# M164B.net
KiCad netlist of a schematic drawn in EAGLE
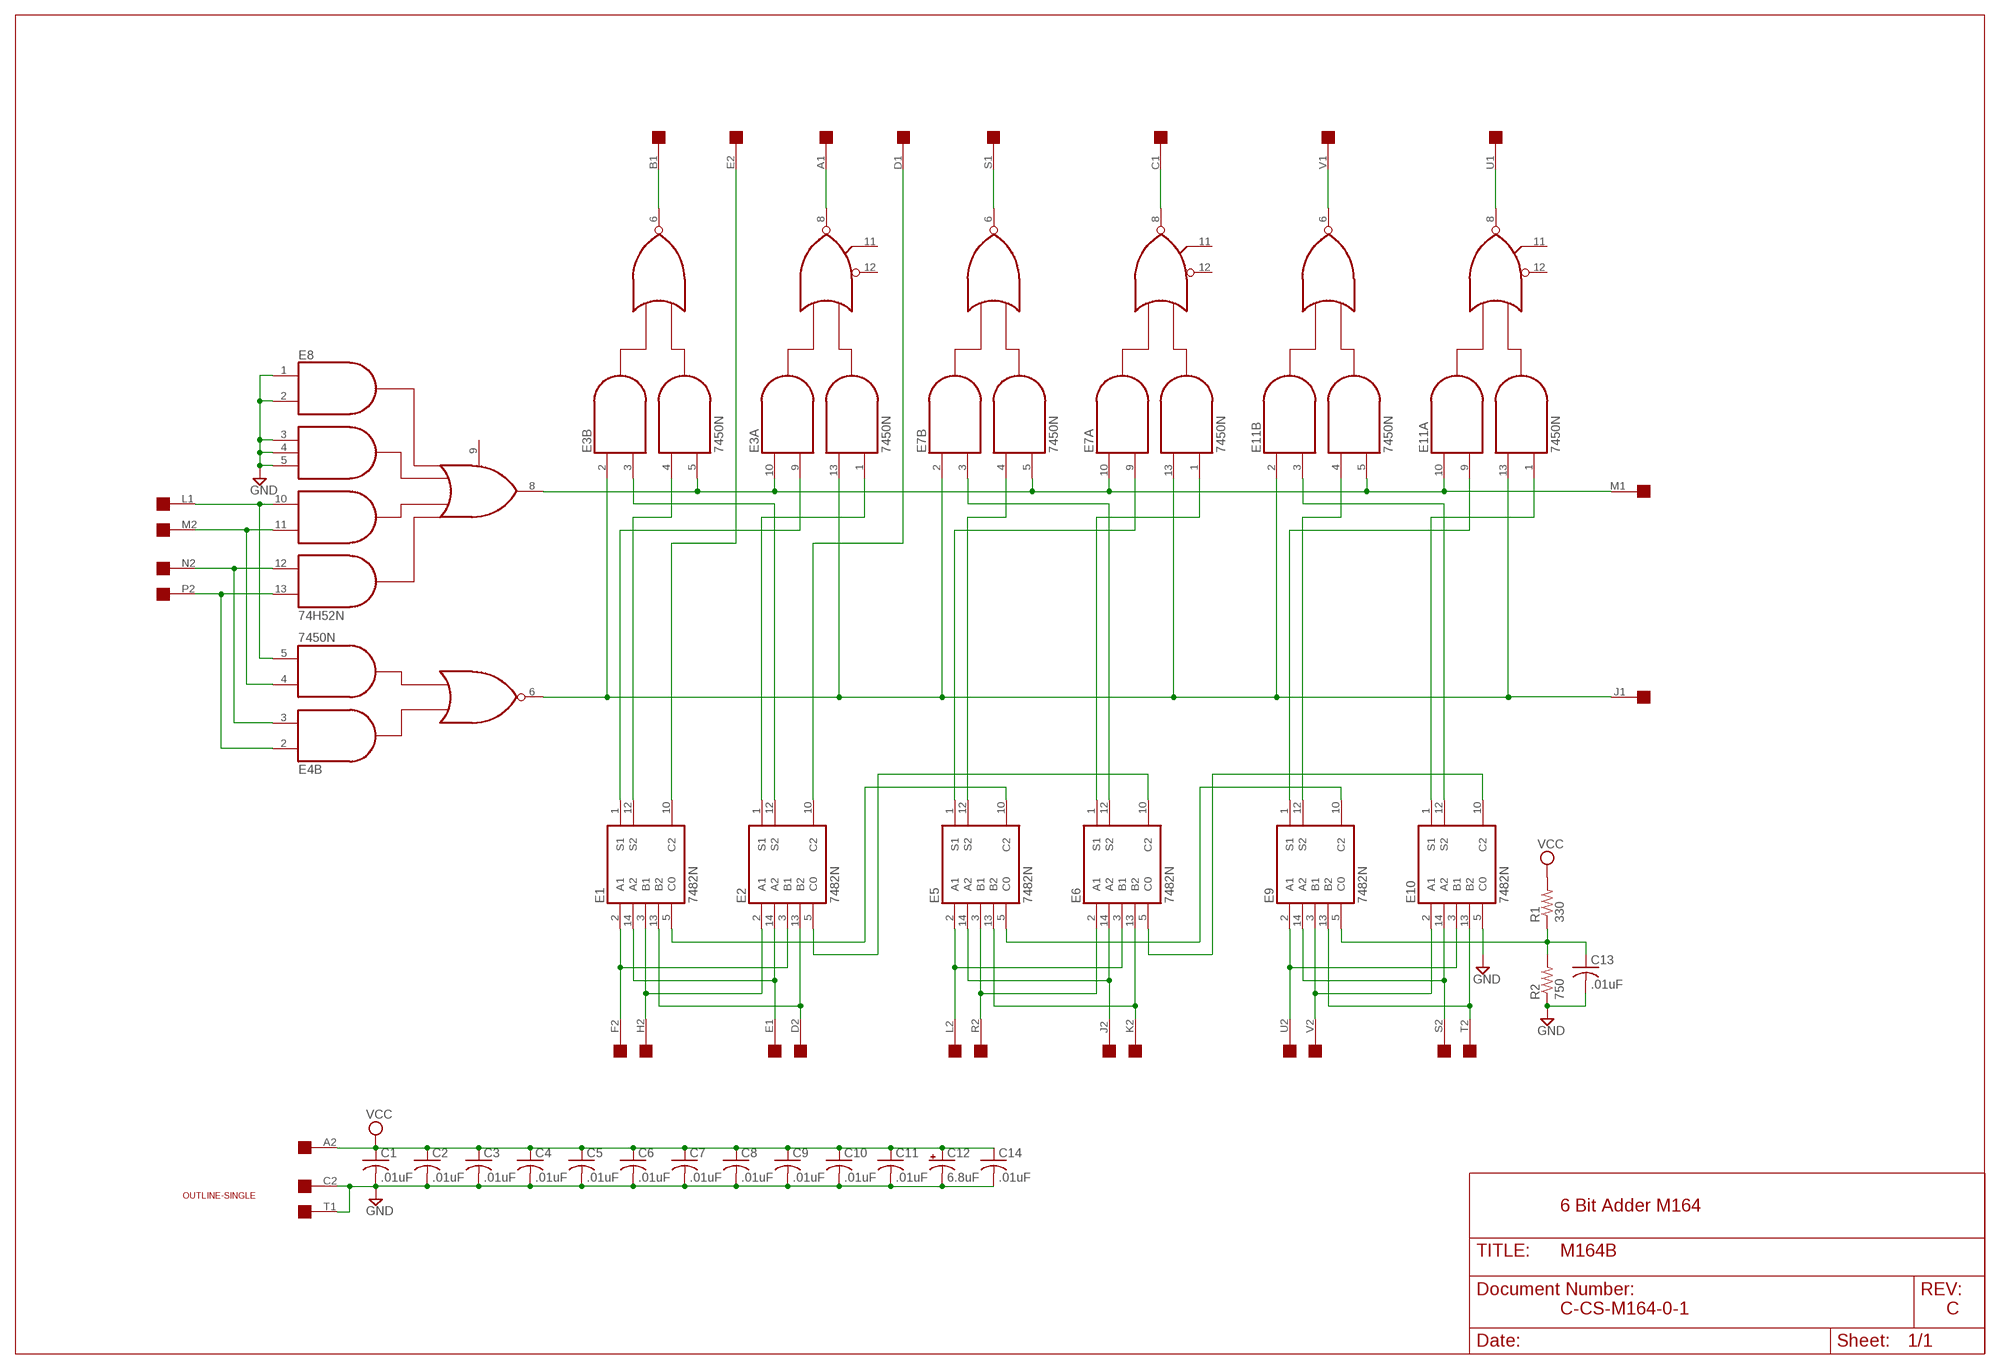
[diagram p0: schematic, sheet 1]

(export (version "E")
  (design (tool "Eeschema 10.0.6"))
  (components
    (comp (ref "C1")
      (value ".01uF")
      (footprint "eagle-import:C050-025X075")
      (libsource (lib "eagle-import") (part "C-US050-025X075"))
    )
    (comp (ref "C2")
      (value ".01uF")
      (footprint "eagle-import:C050-025X075")
      (libsource (lib "eagle-import") (part "C-US050-025X075"))
    )
    (comp (ref "C3")
      (value ".01uF")
      (footprint "eagle-import:C050-025X075")
      (libsource (lib "eagle-import") (part "C-US050-025X075"))
    )
    (comp (ref "C4")
      (value ".01uF")
      (footprint "eagle-import:C050-025X075")
      (libsource (lib "eagle-import") (part "C-US050-025X075"))
    )
    (comp (ref "C5")
      (value ".01uF")
      (footprint "eagle-import:C050-025X075")
      (libsource (lib "eagle-import") (part "C-US050-025X075"))
    )
    (comp (ref "C6")
      (value ".01uF")
      (footprint "eagle-import:C050-025X075")
      (libsource (lib "eagle-import") (part "C-US050-025X075"))
    )
    (comp (ref "C7")
      (value ".01uF")
      (footprint "eagle-import:C050-025X075")
      (libsource (lib "eagle-import") (part "C-US050-025X075"))
    )
    (comp (ref "C8")
      (value ".01uF")
      (footprint "eagle-import:C050-025X075")
      (libsource (lib "eagle-import") (part "C-US050-025X075"))
    )
    (comp (ref "C9")
      (value ".01uF")
      (footprint "eagle-import:C050-025X075")
      (libsource (lib "eagle-import") (part "C-US050-025X075"))
    )
    (comp (ref "C10")
      (value ".01uF")
      (footprint "eagle-import:C050-025X075")
      (libsource (lib "eagle-import") (part "C-US050-025X075"))
    )
    (comp (ref "C11")
      (value ".01uF")
      (footprint "eagle-import:C050-025X075")
      (libsource (lib "eagle-import") (part "C-US050-025X075"))
    )
    (comp (ref "C12")
      (value "6.8uF")
      (footprint "eagle-import:E12-8")
      (libsource (lib "eagle-import") (part "CPOL-USE20-8AXIAL"))
    )
    (comp (ref "C13")
      (value ".01uF")
      (footprint "eagle-import:C050-025X075")
      (libsource (lib "eagle-import") (part "C-US050-025X075"))
    )
    (comp (ref "C14")
      (value ".01uF")
      (footprint "eagle-import:C050-025X075")
      (libsource (lib "eagle-import") (part "C-US050-025X075"))
    )
    (comp (ref "E1")
      (value "7482N")
      (footprint "eagle-import:DIL14")
      (libsource (lib "eagle-import") (part "7482N"))
    )
    (comp (ref "E2")
      (value "7482N")
      (footprint "eagle-import:DIL14")
      (libsource (lib "eagle-import") (part "7482N"))
    )
    (comp (ref "E3")
      (value "7450N")
      (footprint "eagle-import:DIL14")
      (libsource (lib "eagle-import") (part "7450N"))
    )
    (comp (ref "E4")
      (value "7450N")
      (footprint "eagle-import:DIL14")
      (libsource (lib "eagle-import") (part "7450N"))
    )
    (comp (ref "E5")
      (value "7482N")
      (footprint "eagle-import:DIL14")
      (libsource (lib "eagle-import") (part "7482N"))
    )
    (comp (ref "E6")
      (value "7482N")
      (footprint "eagle-import:DIL14")
      (libsource (lib "eagle-import") (part "7482N"))
    )
    (comp (ref "E7")
      (value "7450N")
      (footprint "eagle-import:DIL14")
      (libsource (lib "eagle-import") (part "7450N"))
    )
    (comp (ref "E8")
      (value "74H52N")
      (footprint "eagle-import:DIL14")
      (libsource (lib "eagle-import") (part "7452H"))
    )
    (comp (ref "E9")
      (value "7482N")
      (footprint "eagle-import:DIL14")
      (libsource (lib "eagle-import") (part "7482N"))
    )
    (comp (ref "E10")
      (value "7482N")
      (footprint "eagle-import:DIL14")
      (libsource (lib "eagle-import") (part "7482N"))
    )
    (comp (ref "E11")
      (value "7450N")
      (footprint "eagle-import:DIL14")
      (libsource (lib "eagle-import") (part "7450N"))
    )
    (comp (ref "R1")
      (value "330")
      (footprint "eagle-import:0207_10")
      (libsource (lib "eagle-import") (part "R-US_0207/10"))
    )
    (comp (ref "R2")
      (value "750")
      (footprint "eagle-import:0207_10")
      (libsource (lib "eagle-import") (part "R-US_0207/10"))
    )
    (comp (ref "U$1")
      (value "SINGLE")
      (footprint "eagle-import:EDGE-CON2")
      (libsource (lib "eagle-import") (part "SINGLE"))
    )
    (comp (ref "U$2")
      (value "OUTLINE-SINGLE")
      (footprint "eagle-import:SINGLE")
      (libsource (lib "eagle-import") (part "OUTLINE-SINGLE"))
    )
  )
  (nets
    (net (code "1") (name "GND") (class "Default")
      (node (ref "C1") (pin "2") (pinfunction "2_2") (pintype "passive"))
      (node (ref "C10") (pin "2") (pinfunction "2_2") (pintype "passive"))
      (node (ref "C11") (pin "2") (pinfunction "2_2") (pintype "passive"))
      (node (ref "C12") (pin "-") (pinfunction "-_-") (pintype "passive"))
      (node (ref "C13") (pin "2") (pinfunction "2_2") (pintype "passive"))
      (node (ref "C14") (pin "2") (pinfunction "2_2") (pintype "passive"))
      (node (ref "C2") (pin "2") (pinfunction "2_2") (pintype "passive"))
      (node (ref "C3") (pin "2") (pinfunction "2_2") (pintype "passive"))
      (node (ref "C4") (pin "2") (pinfunction "2_2") (pintype "passive"))
      (node (ref "C5") (pin "2") (pinfunction "2_2") (pintype "passive"))
      (node (ref "C6") (pin "2") (pinfunction "2_2") (pintype "passive"))
      (node (ref "C7") (pin "2") (pinfunction "2_2") (pintype "passive"))
      (node (ref "C8") (pin "2") (pinfunction "2_2") (pintype "passive"))
      (node (ref "C9") (pin "2") (pinfunction "2_2") (pintype "passive"))
      (node (ref "E10") (pin "5") (pinfunction "C0_5") (pintype "input"))
      (node (ref "E8") (pin "1") (pinfunction "I1_1") (pintype "input"))
      (node (ref "E8") (pin "2") (pinfunction "I2_2") (pintype "input"))
      (node (ref "E8") (pin "3") (pinfunction "I3_3") (pintype "input"))
      (node (ref "E8") (pin "4") (pinfunction "I4_4") (pintype "input"))
      (node (ref "E8") (pin "5") (pinfunction "I5_5") (pintype "input"))
      (node (ref "R2") (pin "1") (pinfunction "1_1") (pintype "passive"))
      (node (ref "U$1") (pin "C2") (pinfunction "1_C2") (pintype "bidirectional"))
      (node (ref "U$1") (pin "T1") (pinfunction "1_T1") (pintype "bidirectional"))
    )
    (net (code "2") (name "Net-(E1E-A1)") (class "Default")
      (node (ref "E1") (pin "2") (pinfunction "A1_2") (pintype "input"))
      (node (ref "E2") (pin "3") (pinfunction "B1_3") (pintype "input"))
      (node (ref "U$1") (pin "F2") (pinfunction "1_F2") (pintype "bidirectional"))
    )
    (net (code "3") (name "Net-(E1E-A2)") (class "Default")
      (node (ref "E1") (pin "14") (pinfunction "A2_14") (pintype "input"))
      (node (ref "E2") (pin "14") (pinfunction "A2_14") (pintype "input"))
      (node (ref "U$1") (pin "E1") (pinfunction "1_E1") (pintype "bidirectional"))
    )
    (net (code "4") (name "Net-(E1E-B1)") (class "Default")
      (node (ref "E1") (pin "3") (pinfunction "B1_3") (pintype "input"))
      (node (ref "E2") (pin "2") (pinfunction "A1_2") (pintype "input"))
      (node (ref "U$1") (pin "H2") (pinfunction "1_H2") (pintype "bidirectional"))
    )
    (net (code "5") (name "Net-(E1E-B2)") (class "Default")
      (node (ref "E1") (pin "13") (pinfunction "B2_13") (pintype "input"))
      (node (ref "E2") (pin "13") (pinfunction "B2_13") (pintype "input"))
      (node (ref "U$1") (pin "D2") (pinfunction "1_D2") (pintype "bidirectional"))
    )
    (net (code "6") (name "Net-(E1E-C0)") (class "Default")
      (node (ref "E1") (pin "5") (pinfunction "C0_5") (pintype "input"))
      (node (ref "E5") (pin "10") (pinfunction "C2_10") (pintype "output"))
    )
    (net (code "7") (name "Net-(E1E-C2)") (class "Default")
      (node (ref "E1") (pin "10") (pinfunction "C2_10") (pintype "output"))
      (node (ref "U$1") (pin "E2") (pinfunction "1_E2") (pintype "bidirectional"))
    )
    (net (code "8") (name "Net-(E1E-S1)") (class "Default")
      (node (ref "E1") (pin "1") (pinfunction "S1_1") (pintype "output"))
      (node (ref "E3") (pin "9") (pinfunction "I2_9") (pintype "input"))
    )
    (net (code "9") (name "Net-(E1E-S2)") (class "Default")
      (node (ref "E1") (pin "12") (pinfunction "S2_12") (pintype "output"))
      (node (ref "E3") (pin "4") (pinfunction "I3_4") (pintype "input"))
    )
    (net (code "10") (name "Net-(E2E-C0)") (class "Default")
      (node (ref "E2") (pin "5") (pinfunction "C0_5") (pintype "input"))
      (node (ref "E6") (pin "10") (pinfunction "C2_10") (pintype "output"))
    )
    (net (code "11") (name "Net-(E2E-C2)") (class "Default")
      (node (ref "E2") (pin "10") (pinfunction "C2_10") (pintype "output"))
      (node (ref "U$1") (pin "D1") (pinfunction "1_D1") (pintype "bidirectional"))
    )
    (net (code "12") (name "Net-(E2E-S1)") (class "Default")
      (node (ref "E2") (pin "1") (pinfunction "S1_1") (pintype "output"))
      (node (ref "E3") (pin "1") (pinfunction "I4_1") (pintype "input"))
    )
    (net (code "13") (name "Net-(E2E-S2)") (class "Default")
      (node (ref "E2") (pin "12") (pinfunction "S2_12") (pintype "output"))
      (node (ref "E3") (pin "3") (pinfunction "I2_3") (pintype "input"))
    )
    (net (code "14") (name "Net-(E3A-O)") (class "Default")
      (node (ref "E3") (pin "8") (pinfunction "O_8") (pintype "output"))
      (node (ref "U$1") (pin "A1") (pinfunction "1_A1") (pintype "bidirectional"))
    )
    (net (code "15") (name "Net-(E3B-O)") (class "Default")
      (node (ref "E3") (pin "6") (pinfunction "O_6") (pintype "output"))
      (node (ref "U$1") (pin "B1") (pinfunction "1_B1") (pintype "bidirectional"))
    )
    (net (code "16") (name "Net-(E4B-I1)") (class "Default")
      (node (ref "E4") (pin "2") (pinfunction "I1_2") (pintype "input"))
      (node (ref "E8") (pin "13") (pinfunction "I13_13") (pintype "passive"))
      (node (ref "U$1") (pin "P2") (pinfunction "1_P2") (pintype "bidirectional"))
    )
    (net (code "17") (name "Net-(E4B-I2)") (class "Default")
      (node (ref "E4") (pin "3") (pinfunction "I2_3") (pintype "input"))
      (node (ref "E8") (pin "12") (pinfunction "I12_12") (pintype "input"))
      (node (ref "U$1") (pin "N2") (pinfunction "1_N2") (pintype "bidirectional"))
    )
    (net (code "18") (name "Net-(E4B-I3)") (class "Default")
      (node (ref "E4") (pin "4") (pinfunction "I3_4") (pintype "input"))
      (node (ref "E8") (pin "11") (pinfunction "I11_11") (pintype "input"))
      (node (ref "U$1") (pin "M2") (pinfunction "1_M2") (pintype "bidirectional"))
    )
    (net (code "19") (name "Net-(E4B-I4)") (class "Default")
      (node (ref "E4") (pin "5") (pinfunction "I4_5") (pintype "input"))
      (node (ref "E8") (pin "10") (pinfunction "I10_10") (pintype "input"))
      (node (ref "U$1") (pin "L1") (pinfunction "1_L1") (pintype "bidirectional"))
    )
    (net (code "20") (name "Net-(E5E-A1)") (class "Default")
      (node (ref "E5") (pin "2") (pinfunction "A1_2") (pintype "input"))
      (node (ref "E6") (pin "3") (pinfunction "B1_3") (pintype "input"))
      (node (ref "U$1") (pin "L2") (pinfunction "1_L2") (pintype "bidirectional"))
    )
    (net (code "21") (name "Net-(E5E-A2)") (class "Default")
      (node (ref "E5") (pin "14") (pinfunction "A2_14") (pintype "input"))
      (node (ref "E6") (pin "14") (pinfunction "A2_14") (pintype "input"))
      (node (ref "U$1") (pin "J2") (pinfunction "1_J2") (pintype "bidirectional"))
    )
    (net (code "22") (name "Net-(E5E-B1)") (class "Default")
      (node (ref "E5") (pin "3") (pinfunction "B1_3") (pintype "input"))
      (node (ref "E6") (pin "2") (pinfunction "A1_2") (pintype "input"))
      (node (ref "U$1") (pin "R2") (pinfunction "1_R2") (pintype "bidirectional"))
    )
    (net (code "23") (name "Net-(E5E-B2)") (class "Default")
      (node (ref "E5") (pin "13") (pinfunction "B2_13") (pintype "input"))
      (node (ref "E6") (pin "13") (pinfunction "B2_13") (pintype "input"))
      (node (ref "U$1") (pin "K2") (pinfunction "1_K2") (pintype "bidirectional"))
    )
    (net (code "24") (name "Net-(E5E-C0)") (class "Default")
      (node (ref "E5") (pin "5") (pinfunction "C0_5") (pintype "input"))
      (node (ref "E9") (pin "10") (pinfunction "C2_10") (pintype "output"))
    )
    (net (code "25") (name "Net-(E5E-S1)") (class "Default")
      (node (ref "E5") (pin "1") (pinfunction "S1_1") (pintype "output"))
      (node (ref "E7") (pin "9") (pinfunction "I2_9") (pintype "input"))
    )
    (net (code "26") (name "Net-(E5E-S2)") (class "Default")
      (node (ref "E5") (pin "12") (pinfunction "S2_12") (pintype "output"))
      (node (ref "E7") (pin "4") (pinfunction "I3_4") (pintype "input"))
    )
    (net (code "27") (name "Net-(E6E-S1)") (class "Default")
      (node (ref "E6") (pin "1") (pinfunction "S1_1") (pintype "output"))
      (node (ref "E7") (pin "1") (pinfunction "I4_1") (pintype "input"))
    )
    (net (code "28") (name "Net-(E6E-S2)") (class "Default")
      (node (ref "E6") (pin "12") (pinfunction "S2_12") (pintype "output"))
      (node (ref "E7") (pin "3") (pinfunction "I2_3") (pintype "input"))
    )
    (net (code "29") (name "Net-(E7A-O)") (class "Default")
      (node (ref "E7") (pin "8") (pinfunction "O_8") (pintype "output"))
      (node (ref "U$1") (pin "C1") (pinfunction "1_C1") (pintype "bidirectional"))
    )
    (net (code "30") (name "Net-(E7B-O)") (class "Default")
      (node (ref "E7") (pin "6") (pinfunction "O_6") (pintype "output"))
      (node (ref "U$1") (pin "S1") (pinfunction "1_S1") (pintype "bidirectional"))
    )
    (net (code "31") (name "Net-(E9E-C0)") (class "Default")
      (node (ref "C13") (pin "1") (pinfunction "1_1") (pintype "passive"))
      (node (ref "E9") (pin "5") (pinfunction "C0_5") (pintype "input"))
      (node (ref "R1") (pin "1") (pinfunction "1_1") (pintype "passive"))
      (node (ref "R2") (pin "2") (pinfunction "2_2") (pintype "passive"))
    )
    (net (code "32") (name "Net-(E10E-A1)") (class "Default")
      (node (ref "E10") (pin "2") (pinfunction "A1_2") (pintype "input"))
      (node (ref "E9") (pin "3") (pinfunction "B1_3") (pintype "input"))
      (node (ref "U$1") (pin "V2") (pinfunction "1_V2") (pintype "bidirectional"))
    )
    (net (code "33") (name "Net-(E10E-A2)") (class "Default")
      (node (ref "E10") (pin "14") (pinfunction "A2_14") (pintype "input"))
      (node (ref "E9") (pin "14") (pinfunction "A2_14") (pintype "input"))
      (node (ref "U$1") (pin "S2") (pinfunction "1_S2") (pintype "bidirectional"))
    )
    (net (code "34") (name "Net-(E10E-B1)") (class "Default")
      (node (ref "E10") (pin "3") (pinfunction "B1_3") (pintype "input"))
      (node (ref "E9") (pin "2") (pinfunction "A1_2") (pintype "input"))
      (node (ref "U$1") (pin "U2") (pinfunction "1_U2") (pintype "bidirectional"))
    )
    (net (code "35") (name "Net-(E10E-B2)") (class "Default")
      (node (ref "E10") (pin "13") (pinfunction "B2_13") (pintype "input"))
      (node (ref "E9") (pin "13") (pinfunction "B2_13") (pintype "input"))
      (node (ref "U$1") (pin "T2") (pinfunction "1_T2") (pintype "bidirectional"))
    )
    (net (code "36") (name "Net-(E10E-C2)") (class "Default")
      (node (ref "E10") (pin "10") (pinfunction "C2_10") (pintype "output"))
      (node (ref "E6") (pin "5") (pinfunction "C0_5") (pintype "input"))
    )
    (net (code "37") (name "Net-(E10E-S1)") (class "Default")
      (node (ref "E10") (pin "1") (pinfunction "S1_1") (pintype "output"))
      (node (ref "E11") (pin "1") (pinfunction "I4_1") (pintype "input"))
    )
    (net (code "38") (name "Net-(E10E-S2)") (class "Default")
      (node (ref "E10") (pin "12") (pinfunction "S2_12") (pintype "output"))
      (node (ref "E11") (pin "3") (pinfunction "I2_3") (pintype "input"))
    )
    (net (code "39") (name "Net-(E11A-I1)") (class "Default")
      (node (ref "E11") (pin "10") (pinfunction "I1_10") (pintype "input"))
      (node (ref "E11") (pin "5") (pinfunction "I4_5") (pintype "input"))
      (node (ref "E3") (pin "10") (pinfunction "I1_10") (pintype "input"))
      (node (ref "E3") (pin "5") (pinfunction "I4_5") (pintype "input"))
      (node (ref "E7") (pin "10") (pinfunction "I1_10") (pintype "input"))
      (node (ref "E7") (pin "5") (pinfunction "I4_5") (pintype "input"))
      (node (ref "E8") (pin "8") (pinfunction "O8_8") (pintype "output"))
      (node (ref "U$1") (pin "M1") (pinfunction "1_M1") (pintype "bidirectional"))
    )
    (net (code "40") (name "Net-(E11A-I2)") (class "Default")
      (node (ref "E11") (pin "9") (pinfunction "I2_9") (pintype "input"))
      (node (ref "E9") (pin "1") (pinfunction "S1_1") (pintype "output"))
    )
    (net (code "41") (name "Net-(E11A-I3)") (class "Default")
      (node (ref "E11") (pin "13") (pinfunction "I3_13") (pintype "input"))
      (node (ref "E11") (pin "2") (pinfunction "I1_2") (pintype "input"))
      (node (ref "E3") (pin "13") (pinfunction "I3_13") (pintype "input"))
      (node (ref "E3") (pin "2") (pinfunction "I1_2") (pintype "input"))
      (node (ref "E4") (pin "6") (pinfunction "O_6") (pintype "output"))
      (node (ref "E7") (pin "13") (pinfunction "I3_13") (pintype "input"))
      (node (ref "E7") (pin "2") (pinfunction "I1_2") (pintype "input"))
      (node (ref "U$1") (pin "J1") (pinfunction "1_J1") (pintype "bidirectional"))
    )
    (net (code "42") (name "Net-(E11A-O)") (class "Default")
      (node (ref "E11") (pin "8") (pinfunction "O_8") (pintype "output"))
      (node (ref "U$1") (pin "U1") (pinfunction "1_U1") (pintype "bidirectional"))
    )
    (net (code "43") (name "Net-(E11B-I3)") (class "Default")
      (node (ref "E11") (pin "4") (pinfunction "I3_4") (pintype "input"))
      (node (ref "E9") (pin "12") (pinfunction "S2_12") (pintype "output"))
    )
    (net (code "44") (name "Net-(E11B-O)") (class "Default")
      (node (ref "E11") (pin "6") (pinfunction "O_6") (pintype "output"))
      (node (ref "U$1") (pin "V1") (pinfunction "1_V1") (pintype "bidirectional"))
    )
    (net (code "45") (name "VCC") (class "Default")
      (node (ref "C1") (pin "1") (pinfunction "1_1") (pintype "passive"))
      (node (ref "C10") (pin "1") (pinfunction "1_1") (pintype "passive"))
      (node (ref "C11") (pin "1") (pinfunction "1_1") (pintype "passive"))
      (node (ref "C12") (pin "+") (pinfunction "+_+") (pintype "passive"))
      (node (ref "C14") (pin "1") (pinfunction "1_1") (pintype "passive"))
      (node (ref "C2") (pin "1") (pinfunction "1_1") (pintype "passive"))
      (node (ref "C3") (pin "1") (pinfunction "1_1") (pintype "passive"))
      (node (ref "C4") (pin "1") (pinfunction "1_1") (pintype "passive"))
      (node (ref "C5") (pin "1") (pinfunction "1_1") (pintype "passive"))
      (node (ref "C6") (pin "1") (pinfunction "1_1") (pintype "passive"))
      (node (ref "C7") (pin "1") (pinfunction "1_1") (pintype "passive"))
      (node (ref "C8") (pin "1") (pinfunction "1_1") (pintype "passive"))
      (node (ref "C9") (pin "1") (pinfunction "1_1") (pintype "passive"))
      (node (ref "R1") (pin "2") (pinfunction "2_2") (pintype "passive"))
      (node (ref "U$1") (pin "A2") (pinfunction "1_A2") (pintype "bidirectional"))
    )
    (net (code "46") (name "unconnected-(E3A-I5-Pad12)") (class "Default")
      (node (ref "E3") (pin "12") (pinfunction "I5_12") (pintype "passive"))
    )
    (net (code "47") (name "unconnected-(E3A-I6-Pad11)") (class "Default")
      (node (ref "E3") (pin "11") (pinfunction "I6_11") (pintype "passive"))
    )
    (net (code "48") (name "unconnected-(E7A-I5-Pad12)") (class "Default")
      (node (ref "E7") (pin "12") (pinfunction "I5_12") (pintype "passive"))
    )
    (net (code "49") (name "unconnected-(E7A-I6-Pad11)") (class "Default")
      (node (ref "E7") (pin "11") (pinfunction "I6_11") (pintype "passive"))
    )
    (net (code "50") (name "unconnected-(E8A-I9-Pad9)") (class "Default")
      (node (ref "E8") (pin "9") (pinfunction "I9_9") (pintype "passive"))
    )
    (net (code "51") (name "unconnected-(E11A-I5-Pad12)") (class "Default")
      (node (ref "E11") (pin "12") (pinfunction "I5_12") (pintype "passive"))
    )
    (net (code "52") (name "unconnected-(E11A-I6-Pad11)") (class "Default")
      (node (ref "E11") (pin "11") (pinfunction "I6_11") (pintype "passive"))
    )
  )
)
